# Humidity.net
KiCad netlist of a schematic drawn in Altium Designer
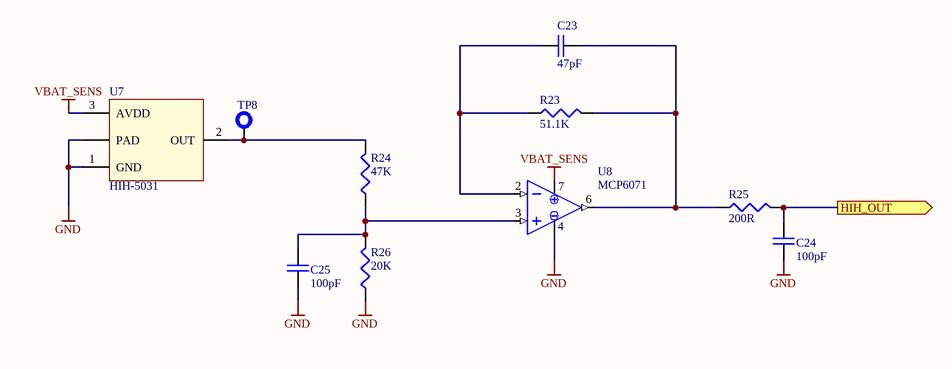
[diagram p0: Humidity.SchDoc]

(export (version "E")
  (design (tool "Eeschema 10.0.6"))
  (components
    (comp (ref "C23")
      (value "47pF")
      (footprint "0603")
      (description "Capacitor")
      (fields (field (name "OWNER") "Nuno Brum"))
      (libsource (lib "Alcetronics_Devices") (part "CAP"))
    )
    (comp (ref "C24")
      (value "100pF")
      (footprint "0603")
      (description "Capacitor")
      (fields (field (name "OWNER") "Nuno Brum"))
      (libsource (lib "Alcetronics_Devices") (part "CAP"))
    )
    (comp (ref "C25")
      (value "100pF")
      (footprint "0603")
      (description "Capacitor")
      (fields (field (name "OWNER") "Nuno Brum"))
      (libsource (lib "Alcetronics_Devices") (part "CAP"))
    )
    (comp (ref "R23")
      (value "51.1K")
      (footprint "0603")
      (description "Resistor")
      (fields (field (name "OWNER") "Nuno Brum"))
      (libsource (lib "Alcetronics_Devices") (part "RES"))
    )
    (comp (ref "R24")
      (value "47K")
      (footprint "0603")
      (description "Resistor")
      (fields (field (name "OWNER") "Nuno Brum"))
      (libsource (lib "Alcetronics_Devices") (part "RES"))
    )
    (comp (ref "R25")
      (value "200R")
      (footprint "0603")
      (description "Resistor")
      (fields (field (name "OWNER") "Nuno Brum"))
      (libsource (lib "Alcetronics_Devices") (part "RES"))
    )
    (comp (ref "R26")
      (value "20K")
      (footprint "0603")
      (description "Resistor")
      (fields (field (name "OWNER") "Nuno Brum"))
      (libsource (lib "Alcetronics_Devices") (part "RES"))
    )
    (comp (ref "TP8")
      (value "Test Point")
      (footprint "TERMINAL")
      (description "Test/Probe Point")
      (fields (field (name "OWNER") "Nuno Brum"))
      (libsource (lib "Alcetronics_EM") (part "TEST-PROBE"))
    )
    (comp (ref "U7")
      (value "HIH-5031")
      (footprint "HIH")
      (description "Low Voltage Humidity Sensor")
      (libsource (lib "Alcetronics_IC") (part "HIH-5031"))
    )
    (comp (ref "U8")
      (value "MCP6071")
      (footprint "SOIC-8")
      (description "Low-Offset Opamp")
      (libsource (lib "Alcetronics_IC") (part "MCP6V26"))
    )
  )
  (nets
    (net (code "1") (name "/HIH_OUT") (class "Default")
      (node (ref "C24") (pin "2") (pinfunction "2_2") (pintype "passive"))
      (node (ref "R25") (pin "2") (pinfunction "2_2") (pintype "passive"))
    )
    (net (code "2") (name "GND") (class "Default")
      (node (ref "C24") (pin "1") (pinfunction "1_1") (pintype "passive"))
      (node (ref "C25") (pin "1") (pinfunction "1_1") (pintype "passive"))
      (node (ref "R26") (pin "1") (pinfunction "1_1") (pintype "passive"))
      (node (ref "U7") (pin "1") (pinfunction "GND_1") (pintype "power_in"))
      (node (ref "U7") (pin "PAD") (pinfunction "PAD_PAD") (pintype "passive"))
      (node (ref "U8") (pin "4") (pinfunction "VSS_4") (pintype "power_in"))
    )
    (net (code "3") (name "Net-(TP8-TP)") (class "Default")
      (node (ref "R24") (pin "2") (pinfunction "2_2") (pintype "passive"))
      (node (ref "TP8") (pin "1") (pinfunction "TP_1") (pintype "passive"))
      (node (ref "U7") (pin "2") (pinfunction "OUT_2") (pintype "passive"))
    )
    (net (code "4") (name "Net-(U8-INN)") (class "Default")
      (node (ref "C23") (pin "1") (pinfunction "1_1") (pintype "passive"))
      (node (ref "R23") (pin "1") (pinfunction "1_1") (pintype "passive"))
      (node (ref "U8") (pin "2") (pinfunction "INN_2") (pintype "input"))
    )
    (net (code "5") (name "Net-(U8-INP)") (class "Default")
      (node (ref "C25") (pin "2") (pinfunction "2_2") (pintype "passive"))
      (node (ref "R24") (pin "1") (pinfunction "1_1") (pintype "passive"))
      (node (ref "R26") (pin "2") (pinfunction "2_2") (pintype "passive"))
      (node (ref "U8") (pin "3") (pinfunction "INP_3") (pintype "input"))
    )
    (net (code "6") (name "Net-(U8-VOUT)") (class "Default")
      (node (ref "C23") (pin "2") (pinfunction "2_2") (pintype "passive"))
      (node (ref "R23") (pin "2") (pinfunction "2_2") (pintype "passive"))
      (node (ref "R25") (pin "1") (pinfunction "1_1") (pintype "passive"))
      (node (ref "U8") (pin "6") (pinfunction "VOUT_6") (pintype "output"))
    )
    (net (code "7") (name "VBAT_SENS") (class "Default")
      (node (ref "U7") (pin "3") (pinfunction "AVDD_3") (pintype "power_in"))
      (node (ref "U8") (pin "7") (pinfunction "VDD_7") (pintype "power_in"))
    )
  )
)
